# 03_-_28PINS_SCHEMATIC.net
KiCad netlist of a schematic drawn in Altium Designer
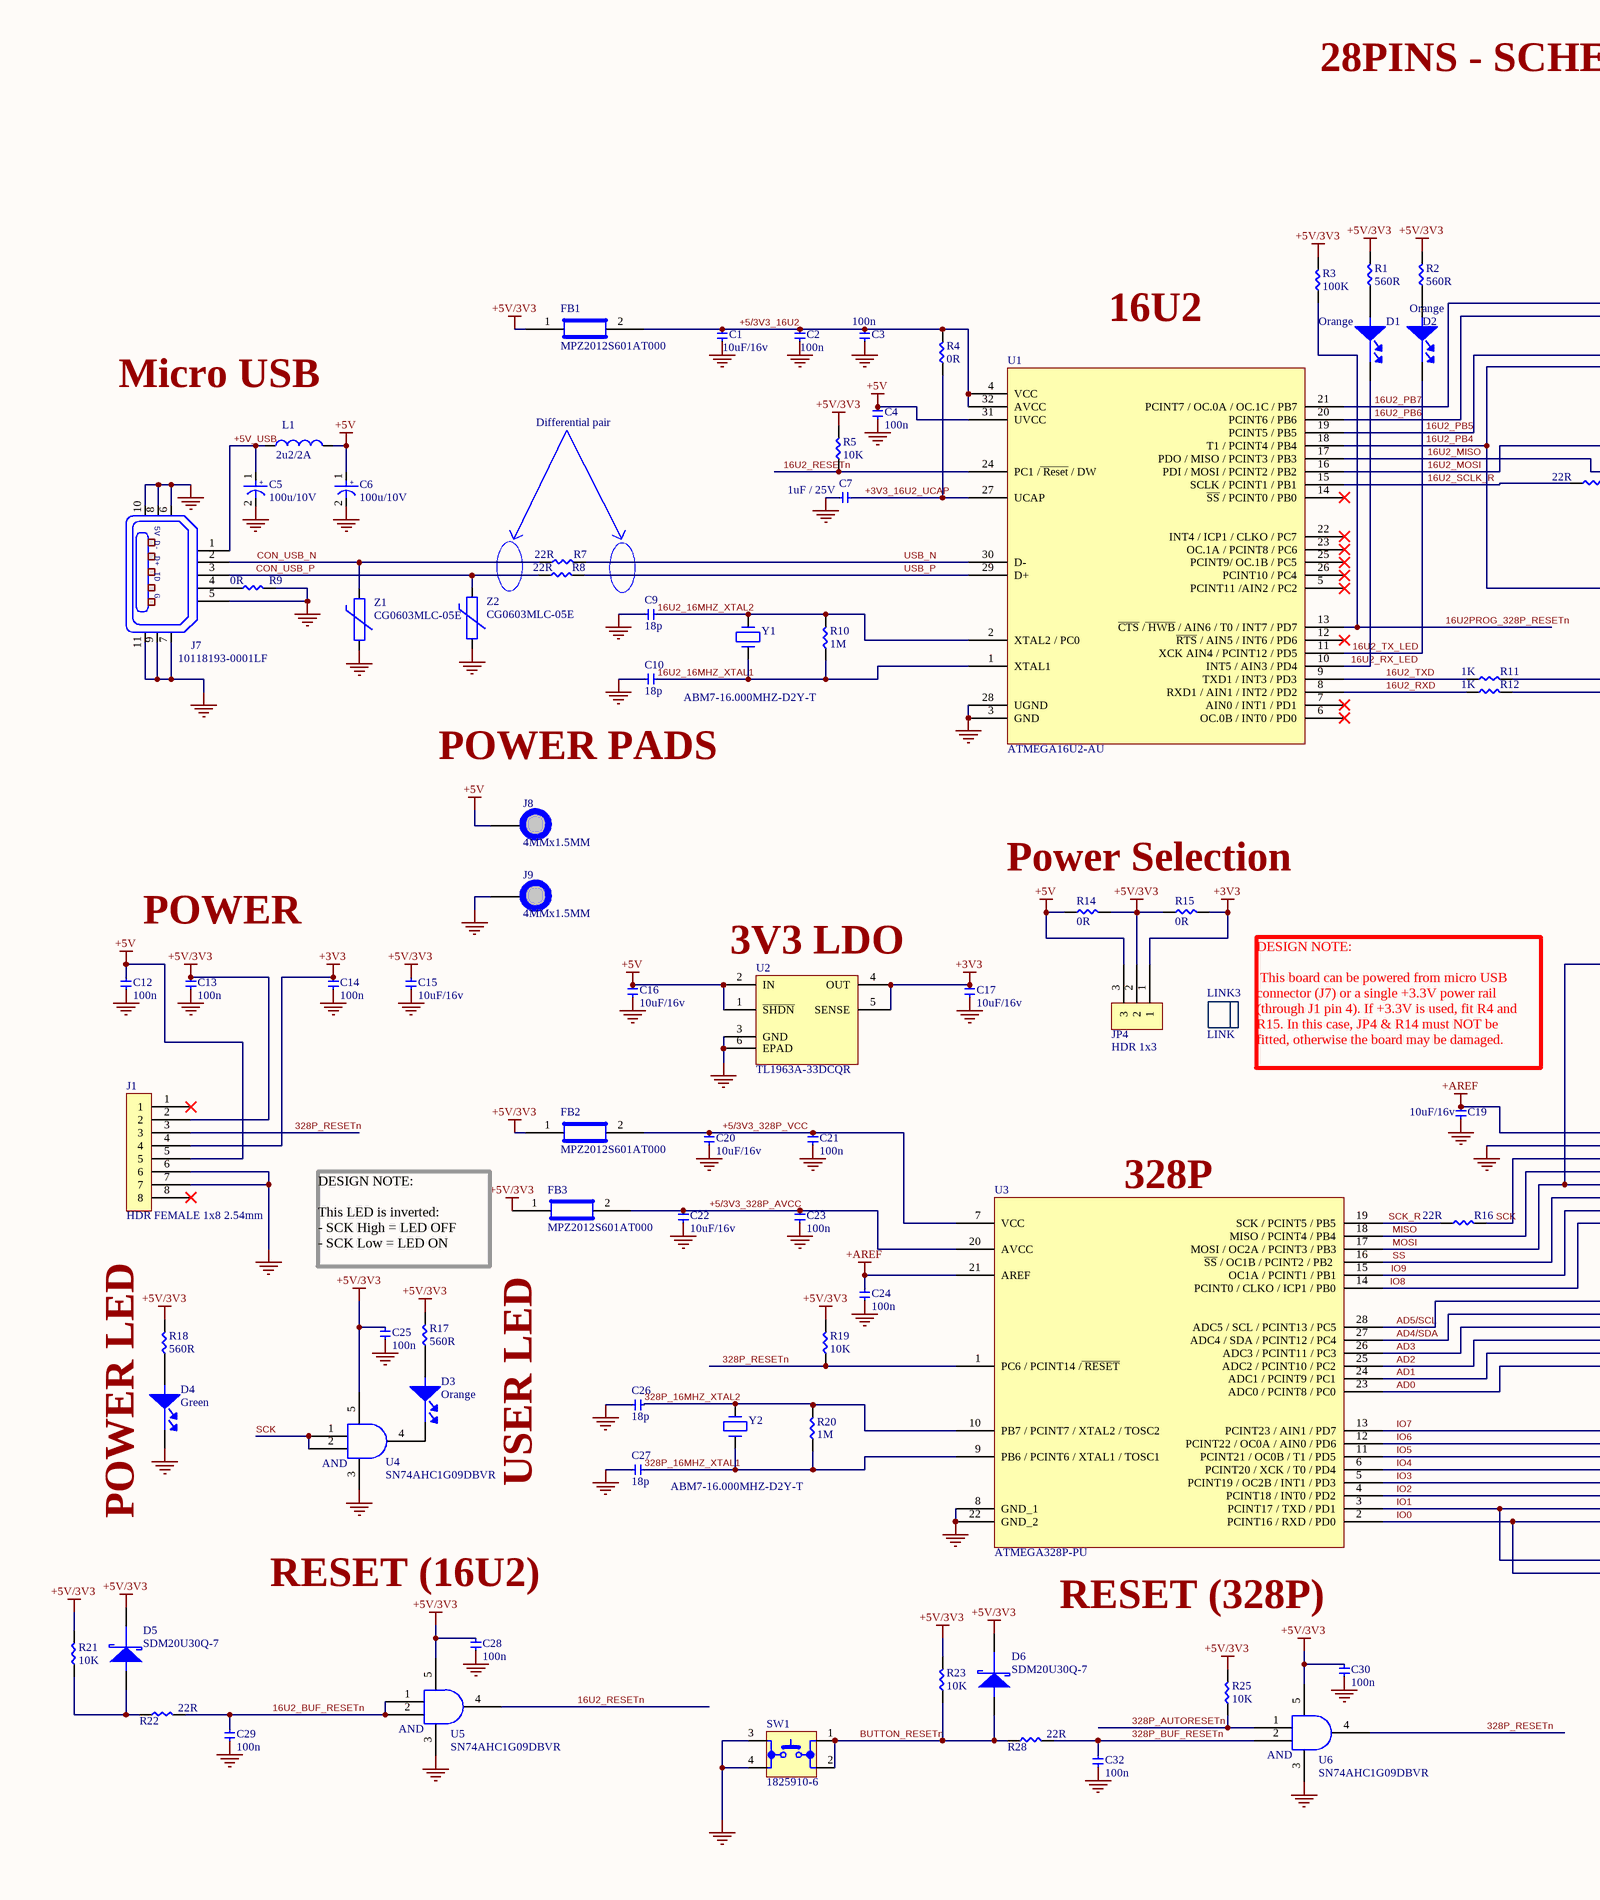
[diagram p0: [03] - 28PINS SCHEMATIC.SchDoc, left]
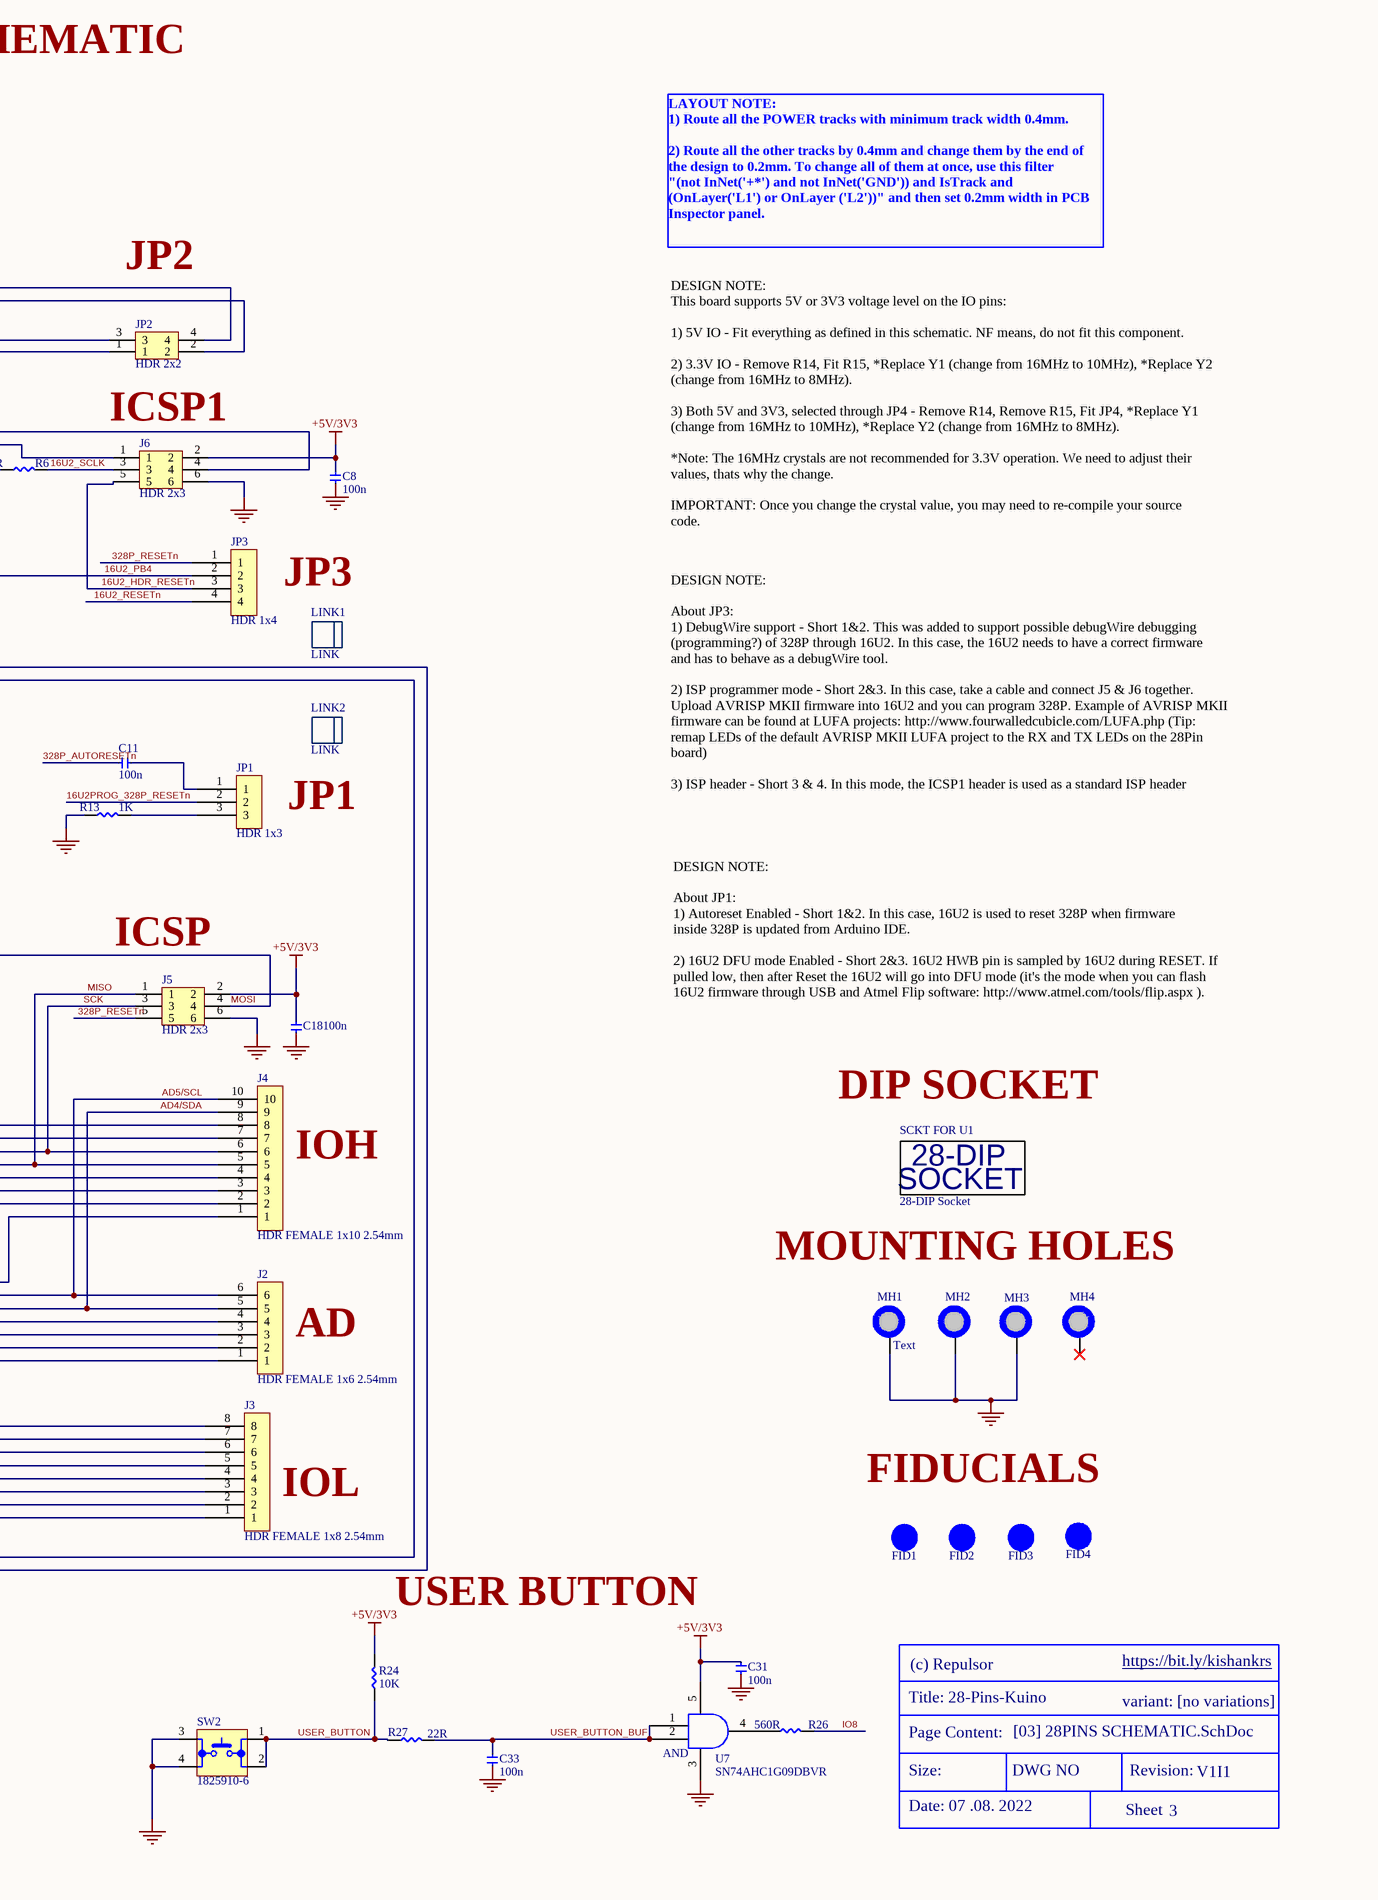
[diagram p1: [03] - 28PINS SCHEMATIC.SchDoc, right]

(export (version "E")
  (design (tool "Eeschema 10.0.6"))
  (components
    (comp (ref "C1")
      (value "10uF/16v")
      (footprint "C0805")
      (fields
        (field (name "MANUFACTURER") "TDK")
        (field (name "MANUFACTURER PART NUMBER") "CGA4J1X5R1C106K125AC")
        (field (name "TOLERANCE") "10%")
      )
      (libsource (lib "28Pins_Project_V1I1") (part "CGA4J1X5R1C106K125AC"))
    )
    (comp (ref "C2")
      (value "100n")
      (footprint "C0805")
      (description "C Series 0805 0.1 uF 50 V ±10 % Tolerance X7R SMT Multilayer Ceramic Capacitor")
      (fields
        (field (name "MANUFACTURER") "TDK")
        (field (name "MANUFACTURER PART NUMBER") "C2012X7R1H104K085AA")
      )
      (libsource (lib "28Pins_Project_V1I1") (part "C2012X7R1H104K085AA"))
    )
    (comp (ref "C3")
      (value "100n")
      (footprint "C0805")
      (description "C Series 0805 0.1 uF 50 V ±10 % Tolerance X7R SMT Multilayer Ceramic Capacitor")
      (fields
        (field (name "MANUFACTURER") "TDK")
        (field (name "MANUFACTURER PART NUMBER") "C2012X7R1H104K085AA")
      )
      (libsource (lib "28Pins_Project_V1I1") (part "C2012X7R1H104K085AA"))
    )
    (comp (ref "C4")
      (value "100n")
      (footprint "C0805")
      (description "C Series 0805 0.1 uF 50 V ±10 % Tolerance X7R SMT Multilayer Ceramic Capacitor")
      (fields
        (field (name "MANUFACTURER") "TDK")
        (field (name "MANUFACTURER PART NUMBER") "C2012X7R1H104K085AA")
      )
      (libsource (lib "28Pins_Project_V1I1") (part "C2012X7R1H104K085AA"))
    )
    (comp (ref "C5")
      (value "100u/10V")
      (footprint "C_ALU_C_SIZE")
      (description "CAP ALUM 100UF 20% 10V SMD")
      (fields
        (field (name "MANUFACTURER") "Panasonic")
        (field (name "MANUFACTURER PART NUMBER") "EEE-1AA101WR")
      )
      (libsource (lib "28Pins_Project_V1I1") (part "EEE-1AA101WR"))
    )
    (comp (ref "C6")
      (value "100u/10V")
      (footprint "C_ALU_C_SIZE")
      (description "CAP ALUM 100UF 20% 10V SMD")
      (fields
        (field (name "MANUFACTURER") "Panasonic")
        (field (name "MANUFACTURER PART NUMBER") "EEE-1AA101WR")
      )
      (libsource (lib "28Pins_Project_V1I1") (part "EEE-1AA101WR"))
    )
    (comp (ref "C7")
      (value "1uF / 25V")
      (footprint "C0805")
      (fields
        (field (name "MANUFACTURER") "TDK")
        (field (name "MANUFACTURER PART NUMBER") "C2012X5R1E105K125AA")
        (field (name "TOLERANCE") "10%")
      )
      (libsource (lib "28Pins_Project_V1I1") (part "C2012X5R1E105K125AA"))
    )
    (comp (ref "C8")
      (value "100n")
      (footprint "C0805")
      (description "C Series 0805 0.1 uF 50 V ±10 % Tolerance X7R SMT Multilayer Ceramic Capacitor")
      (fields
        (field (name "MANUFACTURER") "TDK")
        (field (name "MANUFACTURER PART NUMBER") "C2012X7R1H104K085AA")
      )
      (libsource (lib "28Pins_Project_V1I1") (part "C2012X7R1H104K085AA"))
    )
    (comp (ref "C9")
      (value "18p")
      (footprint "C0805")
      (description "Cap Ceramic 18pF 50V C0G 5% SMD 0805 125C Paper T/R")
      (fields
        (field (name "MANUFACTURER") "KEMET")
        (field (name "MANUFACTURER PART NUMBER") "C0805C180J5GACTU")
      )
      (libsource (lib "28Pins_Project_V1I1") (part "C0805C180J5GACTU"))
    )
    (comp (ref "C10")
      (value "18p")
      (footprint "C0805")
      (description "Cap Ceramic 18pF 50V C0G 5% SMD 0805 125C Paper T/R")
      (fields
        (field (name "MANUFACTURER") "KEMET")
        (field (name "MANUFACTURER PART NUMBER") "C0805C180J5GACTU")
      )
      (libsource (lib "28Pins_Project_V1I1") (part "C0805C180J5GACTU"))
    )
    (comp (ref "C11")
      (value "100n")
      (footprint "C0805")
      (description "C Series 0805 0.1 uF 50 V ±10 % Tolerance X7R SMT Multilayer Ceramic Capacitor")
      (fields
        (field (name "MANUFACTURER") "TDK")
        (field (name "MANUFACTURER PART NUMBER") "C2012X7R1H104K085AA")
      )
      (libsource (lib "28Pins_Project_V1I1") (part "C2012X7R1H104K085AA"))
    )
    (comp (ref "C12")
      (value "100n")
      (footprint "C0805")
      (description "C Series 0805 0.1 uF 50 V ±10 % Tolerance X7R SMT Multilayer Ceramic Capacitor")
      (fields
        (field (name "MANUFACTURER") "TDK")
        (field (name "MANUFACTURER PART NUMBER") "C2012X7R1H104K085AA")
      )
      (libsource (lib "28Pins_Project_V1I1") (part "C2012X7R1H104K085AA"))
    )
    (comp (ref "C13")
      (value "100n")
      (footprint "C0805")
      (description "C Series 0805 0.1 uF 50 V ±10 % Tolerance X7R SMT Multilayer Ceramic Capacitor")
      (fields
        (field (name "MANUFACTURER") "TDK")
        (field (name "MANUFACTURER PART NUMBER") "C2012X7R1H104K085AA")
      )
      (libsource (lib "28Pins_Project_V1I1") (part "C2012X7R1H104K085AA"))
    )
    (comp (ref "C14")
      (value "100n")
      (footprint "C0805")
      (description "C Series 0805 0.1 uF 50 V ±10 % Tolerance X7R SMT Multilayer Ceramic Capacitor")
      (fields
        (field (name "MANUFACTURER") "TDK")
        (field (name "MANUFACTURER PART NUMBER") "C2012X7R1H104K085AA")
      )
      (libsource (lib "28Pins_Project_V1I1") (part "C2012X7R1H104K085AA"))
    )
    (comp (ref "C15")
      (value "10uF/16v")
      (footprint "C0805")
      (fields
        (field (name "MANUFACTURER") "TDK")
        (field (name "MANUFACTURER PART NUMBER") "CGA4J1X5R1C106K125AC")
        (field (name "TOLERANCE") "10%")
      )
      (libsource (lib "28Pins_Project_V1I1") (part "CGA4J1X5R1C106K125AC"))
    )
    (comp (ref "C16")
      (value "10uF/16v")
      (footprint "C0805")
      (fields
        (field (name "MANUFACTURER") "TDK")
        (field (name "MANUFACTURER PART NUMBER") "CGA4J1X5R1C106K125AC")
        (field (name "TOLERANCE") "10%")
      )
      (libsource (lib "28Pins_Project_V1I1") (part "CGA4J1X5R1C106K125AC"))
    )
    (comp (ref "C17")
      (value "10uF/16v")
      (footprint "C0805")
      (fields
        (field (name "MANUFACTURER") "TDK")
        (field (name "MANUFACTURER PART NUMBER") "CGA4J1X5R1C106K125AC")
        (field (name "TOLERANCE") "10%")
      )
      (libsource (lib "28Pins_Project_V1I1") (part "CGA4J1X5R1C106K125AC"))
    )
    (comp (ref "C18")
      (value "100n")
      (footprint "C0805")
      (description "C Series 0805 0.1 uF 50 V ±10 % Tolerance X7R SMT Multilayer Ceramic Capacitor")
      (fields
        (field (name "MANUFACTURER") "TDK")
        (field (name "MANUFACTURER PART NUMBER") "C2012X7R1H104K085AA")
      )
      (libsource (lib "28Pins_Project_V1I1") (part "C2012X7R1H104K085AA"))
    )
    (comp (ref "C19")
      (value "10uF/16v")
      (footprint "C0805")
      (fields
        (field (name "MANUFACTURER") "TDK")
        (field (name "MANUFACTURER PART NUMBER") "CGA4J1X5R1C106K125AC")
        (field (name "TOLERANCE") "10%")
      )
      (libsource (lib "28Pins_Project_V1I1") (part "CGA4J1X5R1C106K125AC"))
    )
    (comp (ref "C20")
      (value "10uF/16v")
      (footprint "C0805")
      (fields
        (field (name "MANUFACTURER") "TDK")
        (field (name "MANUFACTURER PART NUMBER") "CGA4J1X5R1C106K125AC")
        (field (name "TOLERANCE") "10%")
      )
      (libsource (lib "28Pins_Project_V1I1") (part "CGA4J1X5R1C106K125AC"))
    )
    (comp (ref "C21")
      (value "100n")
      (footprint "C0805")
      (description "C Series 0805 0.1 uF 50 V ±10 % Tolerance X7R SMT Multilayer Ceramic Capacitor")
      (fields
        (field (name "MANUFACTURER") "TDK")
        (field (name "MANUFACTURER PART NUMBER") "C2012X7R1H104K085AA")
      )
      (libsource (lib "28Pins_Project_V1I1") (part "C2012X7R1H104K085AA"))
    )
    (comp (ref "C22")
      (value "10uF/16v")
      (footprint "C0805")
      (fields
        (field (name "MANUFACTURER") "TDK")
        (field (name "MANUFACTURER PART NUMBER") "CGA4J1X5R1C106K125AC")
        (field (name "TOLERANCE") "10%")
      )
      (libsource (lib "28Pins_Project_V1I1") (part "CGA4J1X5R1C106K125AC"))
    )
    (comp (ref "C23")
      (value "100n")
      (footprint "C0805")
      (description "C Series 0805 0.1 uF 50 V ±10 % Tolerance X7R SMT Multilayer Ceramic Capacitor")
      (fields
        (field (name "MANUFACTURER") "TDK")
        (field (name "MANUFACTURER PART NUMBER") "C2012X7R1H104K085AA")
      )
      (libsource (lib "28Pins_Project_V1I1") (part "C2012X7R1H104K085AA"))
    )
    (comp (ref "C24")
      (value "100n")
      (footprint "C0805")
      (description "C Series 0805 0.1 uF 50 V ±10 % Tolerance X7R SMT Multilayer Ceramic Capacitor")
      (fields
        (field (name "MANUFACTURER") "TDK")
        (field (name "MANUFACTURER PART NUMBER") "C2012X7R1H104K085AA")
      )
      (libsource (lib "28Pins_Project_V1I1") (part "C2012X7R1H104K085AA"))
    )
    (comp (ref "C25")
      (value "100n")
      (footprint "C0805")
      (description "C Series 0805 0.1 uF 50 V ±10 % Tolerance X7R SMT Multilayer Ceramic Capacitor")
      (fields
        (field (name "MANUFACTURER") "TDK")
        (field (name "MANUFACTURER PART NUMBER") "C2012X7R1H104K085AA")
      )
      (libsource (lib "28Pins_Project_V1I1") (part "C2012X7R1H104K085AA"))
    )
    (comp (ref "C26")
      (value "18p")
      (footprint "C0805")
      (description "Cap Ceramic 18pF 50V C0G 5% SMD 0805 125C Paper T/R")
      (fields
        (field (name "MANUFACTURER") "KEMET")
        (field (name "MANUFACTURER PART NUMBER") "C0805C180J5GACTU")
      )
      (libsource (lib "28Pins_Project_V1I1") (part "C0805C180J5GACTU"))
    )
    (comp (ref "C27")
      (value "18p")
      (footprint "C0805")
      (description "Cap Ceramic 18pF 50V C0G 5% SMD 0805 125C Paper T/R")
      (fields
        (field (name "MANUFACTURER") "KEMET")
        (field (name "MANUFACTURER PART NUMBER") "C0805C180J5GACTU")
      )
      (libsource (lib "28Pins_Project_V1I1") (part "C0805C180J5GACTU"))
    )
    (comp (ref "C28")
      (value "100n")
      (footprint "C0805")
      (description "C Series 0805 0.1 uF 50 V ±10 % Tolerance X7R SMT Multilayer Ceramic Capacitor")
      (fields
        (field (name "MANUFACTURER") "TDK")
        (field (name "MANUFACTURER PART NUMBER") "C2012X7R1H104K085AA")
      )
      (libsource (lib "28Pins_Project_V1I1") (part "C2012X7R1H104K085AA"))
    )
    (comp (ref "C29")
      (value "100n")
      (footprint "C0805")
      (description "C Series 0805 0.1 uF 50 V ±10 % Tolerance X7R SMT Multilayer Ceramic Capacitor")
      (fields
        (field (name "MANUFACTURER") "TDK")
        (field (name "MANUFACTURER PART NUMBER") "C2012X7R1H104K085AA")
      )
      (libsource (lib "28Pins_Project_V1I1") (part "C2012X7R1H104K085AA"))
    )
    (comp (ref "C30")
      (value "100n")
      (footprint "C0805")
      (description "C Series 0805 0.1 uF 50 V ±10 % Tolerance X7R SMT Multilayer Ceramic Capacitor")
      (fields
        (field (name "MANUFACTURER") "TDK")
        (field (name "MANUFACTURER PART NUMBER") "C2012X7R1H104K085AA")
      )
      (libsource (lib "28Pins_Project_V1I1") (part "C2012X7R1H104K085AA"))
    )
    (comp (ref "C31")
      (value "100n")
      (footprint "C0805")
      (description "C Series 0805 0.1 uF 50 V ±10 % Tolerance X7R SMT Multilayer Ceramic Capacitor")
      (fields
        (field (name "MANUFACTURER") "TDK")
        (field (name "MANUFACTURER PART NUMBER") "C2012X7R1H104K085AA")
      )
      (libsource (lib "28Pins_Project_V1I1") (part "C2012X7R1H104K085AA"))
    )
    (comp (ref "C32")
      (value "100n")
      (footprint "C0805")
      (description "C Series 0805 0.1 uF 50 V ±10 % Tolerance X7R SMT Multilayer Ceramic Capacitor")
      (fields
        (field (name "MANUFACTURER") "TDK")
        (field (name "MANUFACTURER PART NUMBER") "C2012X7R1H104K085AA")
      )
      (libsource (lib "28Pins_Project_V1I1") (part "C2012X7R1H104K085AA"))
    )
    (comp (ref "C33")
      (value "100n")
      (footprint "C0805")
      (description "C Series 0805 0.1 uF 50 V ±10 % Tolerance X7R SMT Multilayer Ceramic Capacitor")
      (fields
        (field (name "MANUFACTURER") "TDK")
        (field (name "MANUFACTURER PART NUMBER") "C2012X7R1H104K085AA")
      )
      (libsource (lib "28Pins_Project_V1I1") (part "C2012X7R1H104K085AA"))
    )
    (comp (ref "D1")
      (value "Orange")
      (footprint "LED_0603")
      (description "Smartled Orange Lc")
      (fields
        (field (name "MANUFACTURER") "Osram Opto")
        (field (name "MANUFACTURER PART NUMBER") "LOL29K-H2K1-24-Z")
      )
      (libsource (lib "28Pins_Project_V1I1") (part "LOL29K-H2K1-24-Z"))
    )
    (comp (ref "D2")
      (value "Orange")
      (footprint "LED_0603")
      (description "Smartled Orange Lc")
      (fields
        (field (name "MANUFACTURER") "Osram Opto")
        (field (name "MANUFACTURER PART NUMBER") "LOL29K-H2K1-24-Z")
      )
      (libsource (lib "28Pins_Project_V1I1") (part "LOL29K-H2K1-24-Z"))
    )
    (comp (ref "D3")
      (value "Orange")
      (footprint "LED_0603")
      (description "Smartled Orange Lc")
      (fields
        (field (name "MANUFACTURER") "Osram Opto")
        (field (name "MANUFACTURER PART NUMBER") "LOL29K-H2K1-24-Z")
      )
      (libsource (lib "28Pins_Project_V1I1") (part "LOL29K-H2K1-24-Z"))
    )
    (comp (ref "D4")
      (value "Green")
      (footprint "LED_0603")
      (description "Green 574nm LED Indication - Discrete 1.9V 0603 (1608 Metric)")
      (fields (field (name "MANUFACTURER") "Bivar") (field (name "MANUFACTURER PART NUMBER") "SM0603GCL"))
      (libsource (lib "28Pins_Project_V1I1") (part "SM0603GCL"))
    )
    (comp (ref "D5")
      (value "SDM20U30Q-7")
      (footprint "SOD523")
      (description "Schottky Rectifier, 30V, 0.2A, Sod-523 Rohs Compliant: Yes")
      (fields (field (name "MANUFACTURER") "Diodes"))
      (libsource (lib "28Pins_Project_V1I1") (part "SDM20U30Q-7"))
    )
    (comp (ref "D6")
      (value "SDM20U30Q-7")
      (footprint "SOD523")
      (description "Schottky Rectifier, 30V, 0.2A, Sod-523 Rohs Compliant: Yes")
      (fields (field (name "MANUFACTURER") "Diodes"))
      (libsource (lib "28Pins_Project_V1I1") (part "SDM20U30Q-7"))
    )
    (comp (ref "FB1")
      (value "MPZ2012S601AT000")
      (footprint "C0805")
      (description "0805 600Ω ±25% DCR=0.1Ω 2A")
      (fields (field (name "MANUFACTURER") "TDK"))
      (libsource (lib "28Pins_Project_V1I1") (part "MPZ2012S601AT000"))
    )
    (comp (ref "FB2")
      (value "MPZ2012S601AT000")
      (footprint "C0805")
      (description "0805 600Ω ±25% DCR=0.1Ω 2A")
      (fields (field (name "MANUFACTURER") "TDK"))
      (libsource (lib "28Pins_Project_V1I1") (part "MPZ2012S601AT000"))
    )
    (comp (ref "FB3")
      (value "MPZ2012S601AT000")
      (footprint "C0805")
      (description "0805 600Ω ±25% DCR=0.1Ω 2A")
      (fields (field (name "MANUFACTURER") "TDK"))
      (libsource (lib "28Pins_Project_V1I1") (part "MPZ2012S601AT000"))
    )
    (comp (ref "FID1")
      (value "FID_1MMC")
      (footprint "FID_40x120D")
      (description "Fiducial 40mil Diameter, 120mil Mask")
      (libsource (lib "28Pins_Project_V1I1") (part "FID_1MMC"))
    )
    (comp (ref "FID2")
      (value "FID_1MMC")
      (footprint "FID_40x120D")
      (description "Fiducial 40mil Diameter, 120mil Mask")
      (libsource (lib "28Pins_Project_V1I1") (part "FID_1MMC"))
    )
    (comp (ref "FID3")
      (value "FID_1MMC")
      (footprint "FID_40x120D")
      (description "Fiducial 40mil Diameter, 120mil Mask")
      (libsource (lib "28Pins_Project_V1I1") (part "FID_1MMC"))
    )
    (comp (ref "FID4")
      (value "FID_1MMC")
      (footprint "FID_40x120D")
      (description "Fiducial 40mil Diameter, 120mil Mask")
      (libsource (lib "28Pins_Project_V1I1") (part "FID_1MMC"))
    )
    (comp (ref "J1")
      (value "HDR FEMALE 1x8 2.54mm")
      (footprint "Hdr_Female_1x8_2.54mm")
      (description "2.54mm (0.1\") Pitch SIL Vertical PC Tail Socket Assembly, selective gold + tin, 8 contacts")
      (fields (field (name "MANUFACTURER") "Harwin") (field (name "MANUFACTURER PART NUMBER") "M20-7820842"))
      (libsource (lib "") (part "M20-7820842_1"))
    )
    (comp (ref "J2")
      (value "HDR FEMALE 1x6 2.54mm")
      (footprint "Hdr_Female_1x6_2.54mm")
      (description "2.54mm (0.1\") Pitch SIL Vertical PC Tail Socket Assembly, tin, 6 contacts")
      (fields (field (name "MANUFACTURER") "Harwin") (field (name "MANUFACTURER PART NUMBER") "M20-7820646"))
      (libsource (lib "28Pins_Project_V1I1") (part "M20-7820646"))
    )
    (comp (ref "J3")
      (value "HDR FEMALE 1x8 2.54mm")
      (footprint "Hdr_Female_1x8_2.54mm")
      (description "2.54mm (0.1\") Pitch SIL Vertical PC Tail Socket Assembly, selective gold + tin, 8 contacts")
      (fields (field (name "MANUFACTURER") "Harwin") (field (name "MANUFACTURER PART NUMBER") "M20-7820842"))
      (libsource (lib "28Pins_Project_V1I1") (part "M20-7820842"))
    )
    (comp (ref "J4")
      (value "HDR FEMALE 1x10 2.54mm")
      (footprint "Hdr_Female_1x10_2.54mm")
      (description "2.54mm (0.1\") Pitch SIL Vertical PC Tail Socket Assembly, tin, 10 contacts")
      (fields (field (name "MANUFACTURER") "Harwin") (field (name "MANUFACTURER PART NUMBER") "M20-7821046"))
      (libsource (lib "28Pins_Project_V1I1") (part "M20-7821046"))
    )
    (comp (ref "J5")
      (value "HDR 2x3")
      (footprint "HDR_2x3_2.54MM")
      (description "2 Row 6 Position 2.54 mm Straight Unshrouded Male Pin Header")
      (fields
        (field (name "MANUFACTURER") "Amphenol Communications Solutions")
        (field (name "MANUFACTURER PART NUMBER") "67997-206HLF")
      )
      (libsource (lib "28Pins_Project_V1I1") (part "67997-206HLF"))
    )
    (comp (ref "J6")
      (value "HDR 2x3")
      (footprint "HDR_2x3_2.54MM")
      (description "2 Row 6 Position 2.54 mm Straight Unshrouded Male Pin Header")
      (fields
        (field (name "MANUFACTURER") "Amphenol Communications Solutions")
        (field (name "MANUFACTURER PART NUMBER") "67997-206HLF")
      )
      (libsource (lib "28Pins_Project_V1I1") (part "67997-206HLF"))
    )
    (comp (ref "J7")
      (value "10118193-0001LF")
      (footprint "10118193")
      (description "FCI Right Angle Surface Mount Mount Female USB Connector; 100 V ac; 1.8A")
      (fields (field (name "MANUFACTURER") "Amphenol ICC / FCI"))
      (libsource (lib "28Pins_Project_V1I1") (part "10118193-0001LF"))
    )
    (comp (ref "J8")
      (value "4MMx1.5MM")
      (footprint "PAD_WITH_HOLE_4MMx1.5MM")
      (description "pad with a hole 4mm x 1.5 mm")
      (libsource (lib "28Pins_Project_V1I1") (part "PAD_WITH_HOLE_4MMx1.5MM"))
    )
    (comp (ref "J9")
      (value "4MMx1.5MM")
      (footprint "PAD_WITH_HOLE_4MMx1.5MM")
      (description "pad with a hole 4mm x 1.5 mm")
      (libsource (lib "28Pins_Project_V1I1") (part "PAD_WITH_HOLE_4MMx1.5MM"))
    )
    (comp (ref "JP1")
      (value "HDR 1x3")
      (footprint "Hdr_1x3_2.54mm")
      (description "Conn Unshrouded Header HDR 3 POS 2.54mm Solder ST Top Entry Thru-Hole BergStik® Automotive Bulk")
      (fields
        (field (name "MANUFACTURER") "Amphenol ICC / FCI")
        (field (name "MANUFACTURER PART NUMBER") "68000-103HLF")
      )
      (libsource (lib "28Pins_Project_V1I1") (part "68000-103HLF"))
    )
    (comp (ref "JP2")
      (value "HDR 2x2")
      (footprint "HDR_2x2_2.54MM")
      (description "Conn Unshrouded Header HDR 4 POS 2.54mm Solder ST Thru-Hole Poly Bag")
      (fields
        (field (name "MANUFACTURER") "Amphenol ICC / FCI")
        (field (name "MANUFACTURER PART NUMBER") "68491-104HLF")
      )
      (libsource (lib "28Pins_Project_V1I1") (part "68491-104HLF"))
    )
    (comp (ref "JP3")
      (value "HDR 1x4")
      (footprint "HDR_1x4_2.54mm")
      (description "Conn Unshrouded Header HDR 4 POS 2.54mm Solder ST Thru-Hole Bag")
      (fields
        (field (name "MANUFACTURER") "Amphenol ICC / FCI")
        (field (name "MANUFACTURER PART NUMBER") "68001-204HLF")
      )
      (libsource (lib "28Pins_Project_V1I1") (part "68001-204HLF"))
    )
    (comp (ref "JP4")
      (value "HDR 1x3")
      (footprint "Hdr_1x3_2.54mm")
      (description "Conn Unshrouded Header HDR 3 POS 2.54mm Solder ST Top Entry Thru-Hole BergStik® Automotive Bulk")
      (fields
        (field (name "MANUFACTURER") "Amphenol ICC / FCI")
        (field (name "MANUFACTURER PART NUMBER") "68000-103HLF")
      )
      (libsource (lib "") (part "68000-103HLF_1"))
    )
    (comp (ref "L1")
      (value "2u2/2A")
      (footprint "C1210_IND")
      (description "Inductor RF Chip Wirewound 2.2uH 20% 100KHz 1.13A 0.104Ohm DCR 1210 T/R")
      (fields
        (field (name "MANUFACTURER") "KEMET")
        (field (name "MANUFACTURER PART NUMBER") "L1210R2R2MDWIT")
      )
      (libsource (lib "28Pins_Project_V1I1") (part "L1210R2R2MDWIT"))
    )
    (comp (ref "LINK1")
      (value "LINK")
      (description "2 Position 2.54 mm Centerline Single Circuit Open Top Jumper")
      (fields
        (field (name "MANUFACTURER") "Sullins")
        (field (name "MANUFACTURER PART NUMBER") "QPC02SXGN-RC")
      )
      (libsource (lib "28Pins_Project_V1I1") (part "QPC02SXGN-RC"))
    )
    (comp (ref "LINK2")
      (value "LINK")
      (description "2 Position 2.54 mm Centerline Single Circuit Open Top Jumper")
      (fields
        (field (name "MANUFACTURER") "Sullins")
        (field (name "MANUFACTURER PART NUMBER") "QPC02SXGN-RC")
      )
      (libsource (lib "28Pins_Project_V1I1") (part "QPC02SXGN-RC"))
    )
    (comp (ref "LINK3")
      (value "LINK")
      (description "2 Position 2.54 mm Centerline Single Circuit Open Top Jumper")
      (fields
        (field (name "MANUFACTURER") "Sullins")
        (field (name "MANUFACTURER PART NUMBER") "QPC02SXGN-RC")
      )
      (libsource (lib "28Pins_Project_V1I1") (part "QPC02SXGN-RC"))
    )
    (comp (ref "MH1")
      (value "MH_7.4MMC_3.2MMD")
      (footprint "MH_7.4MMD_3.2MMD")
      (description "Mounting Hole 7.4mm Diameter, 3.2mm Drill")
      (libsource (lib "28Pins_Project_V1I1") (part "MH_7.4MMC_3.2MMD"))
    )
    (comp (ref "MH2")
      (value "MH_7.4MMC_3.2MMD")
      (footprint "MH_7.4MMD_3.2MMD")
      (description "Mounting Hole 7.4mm Diameter, 3.2mm Drill")
      (libsource (lib "28Pins_Project_V1I1") (part "MH_7.4MMC_3.2MMD"))
    )
    (comp (ref "MH3")
      (value "MH_7.4MMC_3.2MMD")
      (footprint "MH_7.4MMD_3.2MMD")
      (description "Mounting Hole 7.4mm Diameter, 3.2mm Drill")
      (libsource (lib "28Pins_Project_V1I1") (part "MH_7.4MMC_3.2MMD"))
    )
    (comp (ref "MH4")
      (value "MH_7.4MMNC_3.2MMD")
      (footprint "MH_7.4MMNC_3.2MMD_NON_COPPER_NPTH")
      (description "Hole 7.4mm Diameter(Non Copper), 3.2mm Drill NPTH")
      (libsource (lib "28Pins_Project_V1I1") (part "MH_7.4MMNC_3.2MMD"))
    )
    (comp (ref "R1")
      (value "560R")
      (footprint "R0805")
      (description "Res General Purpose Thick Film 0805 560 Ohm 1% 1/8W ±100ppm/°C Molded Paper T/R")
      (fields
        (field (name "MANUFACTURER") "Yageo")
        (field (name "MANUFACTURER PART NUMBER") "RC0805FR-07560RL")
      )
      (libsource (lib "28Pins_Project_V1I1") (part "RC0805FR-07560RL"))
    )
    (comp (ref "R2")
      (value "560R")
      (footprint "R0805")
      (description "Res General Purpose Thick Film 0805 560 Ohm 1% 1/8W ±100ppm/°C Molded Paper T/R")
      (fields
        (field (name "MANUFACTURER") "Yageo")
        (field (name "MANUFACTURER PART NUMBER") "RC0805FR-07560RL")
      )
      (libsource (lib "28Pins_Project_V1I1") (part "RC0805FR-07560RL"))
    )
    (comp (ref "R3")
      (value "100K")
      (footprint "R0805")
      (description "Res Thick Film 0805 100K Ohm 1% 1/8W ±100ppm/°C Molded SMD Paper T/R")
      (fields
        (field (name "MANUFACTURER") "Yageo")
        (field (name "MANUFACTURER PART NUMBER") "RC0805FR-07100KL")
      )
      (libsource (lib "28Pins_Project_V1I1") (part "RC0805FR-07100KL"))
    )
    (comp (ref "R4")
      (value "0R")
      (footprint "R0805")
      (description "Surface Mount Thick Film Resistor, RC Series, 125 mW, - 5%, 150 V, 0805 [2012 Metric]")
      (fields
        (field (name "MANUFACTURER") "Yageo")
        (field (name "MANUFACTURER PART NUMBER") "RC0805JR-070RL")
      )
      (libsource (lib "28Pins_Project_V1I1") (part "RC0805JR-070RL"))
    )
    (comp (ref "R5")
      (value "10K")
      (footprint "R0805")
      (description "Res Thick Film 0805 10K Ohm 1% 0.125W(1/8W) +/-100ppm/C Epoxy Pad SMD T/R")
      (fields
        (field (name "MANUFACTURER") "Yageo")
        (field (name "MANUFACTURER PART NUMBER") "RC0805FR-0710KL")
      )
      (libsource (lib "28Pins_Project_V1I1") (part "RC0805FR-0710KL"))
    )
    (comp (ref "R6")
      (value "22R")
      (footprint "R0805")
      (description "Res Thick Film 0805 220 Ohm 1% 1/8W +/-100ppm/ßC Molded SMD Paper T/R")
      (fields
        (field (name "MANUFACTURER") "Yageo")
        (field (name "MANUFACTURER PART NUMBER") "RC0805FR-07220RL")
      )
      (libsource (lib "28Pins_Project_V1I1") (part "RC0805FR-07220RL"))
    )
    (comp (ref "R7")
      (value "22R")
      (footprint "R0805")
      (description "Res Thick Film 0805 220 Ohm 1% 1/8W +/-100ppm/ßC Molded SMD Paper T/R")
      (fields
        (field (name "MANUFACTURER") "Yageo")
        (field (name "MANUFACTURER PART NUMBER") "RC0805FR-07220RL")
      )
      (libsource (lib "28Pins_Project_V1I1") (part "RC0805FR-07220RL"))
    )
    (comp (ref "R8")
      (value "22R")
      (footprint "R0805")
      (description "Res Thick Film 0805 220 Ohm 1% 1/8W +/-100ppm/ßC Molded SMD Paper T/R")
      (fields
        (field (name "MANUFACTURER") "Yageo")
        (field (name "MANUFACTURER PART NUMBER") "RC0805FR-07220RL")
      )
      (libsource (lib "28Pins_Project_V1I1") (part "RC0805FR-07220RL"))
    )
    (comp (ref "R9")
      (value "0R")
      (footprint "R0805")
      (description "Surface Mount Thick Film Resistor, RC Series, 125 mW, - 5%, 150 V, 0805 [2012 Metric]")
      (fields
        (field (name "MANUFACTURER") "Yageo")
        (field (name "MANUFACTURER PART NUMBER") "RC0805JR-070RL")
      )
      (libsource (lib "28Pins_Project_V1I1") (part "RC0805JR-070RL"))
    )
    (comp (ref "R10")
      (value "1M")
      (footprint "R0805")
      (description "Res Thick Film 0805 1M Ohm 1% 0.125W(1/8W) ±100ppm/C Pad SMD T/R")
      (fields
        (field (name "MANUFACTURER") "Yageo Phycomp")
        (field (name "MANUFACTURER PART NUMBER") "RC0805FR-071ML")
      )
      (libsource (lib "28Pins_Project_V1I1") (part "RC0805FR-071ML"))
    )
    (comp (ref "R11")
      (value "1K")
      (footprint "R0805")
      (description "RES SMD 1K OHM 1% 1/8W 0805")
      (fields
        (field (name "MANUFACTURER") "Yageo")
        (field (name "MANUFACTURER PART NUMBER") "RC0805FR-071KL")
      )
      (libsource (lib "28Pins_Project_V1I1") (part "RC0805FR-071KL"))
    )
    (comp (ref "R12")
      (value "1K")
      (footprint "R0805")
      (description "RES SMD 1K OHM 1% 1/8W 0805")
      (fields
        (field (name "MANUFACTURER") "Yageo")
        (field (name "MANUFACTURER PART NUMBER") "RC0805FR-071KL")
      )
      (libsource (lib "28Pins_Project_V1I1") (part "RC0805FR-071KL"))
    )
    (comp (ref "R13")
      (value "1K")
      (footprint "R0805")
      (description "RES SMD 1K OHM 1% 1/8W 0805")
      (fields
        (field (name "MANUFACTURER") "Yageo")
        (field (name "MANUFACTURER PART NUMBER") "RC0805FR-071KL")
      )
      (libsource (lib "28Pins_Project_V1I1") (part "RC0805FR-071KL"))
    )
    (comp (ref "R14")
      (value "0R")
      (footprint "R0805")
      (description "Surface Mount Thick Film Resistor, RC Series, 125 mW, - 5%, 150 V, 0805 [2012 Metric]")
      (fields
        (field (name "MANUFACTURER") "Yageo")
        (field (name "MANUFACTURER PART NUMBER") "RC0805JR-070RL")
      )
      (libsource (lib "28Pins_Project_V1I1") (part "RC0805JR-070RL"))
    )
    (comp (ref "R15")
      (value "0R")
      (footprint "R0805")
      (description "Surface Mount Thick Film Resistor, RC Series, 125 mW, - 5%, 150 V, 0805 [2012 Metric]")
      (fields
        (field (name "MANUFACTURER") "Yageo")
        (field (name "MANUFACTURER PART NUMBER") "RC0805JR-070RL")
      )
      (libsource (lib "28Pins_Project_V1I1") (part "RC0805JR-070RL"))
    )
    (comp (ref "R16")
      (value "22R")
      (footprint "R0805")
      (description "Res Thick Film 0805 220 Ohm 1% 1/8W +/-100ppm/ßC Molded SMD Paper T/R")
      (fields
        (field (name "MANUFACTURER") "Yageo")
        (field (name "MANUFACTURER PART NUMBER") "RC0805FR-07220RL")
      )
      (libsource (lib "28Pins_Project_V1I1") (part "RC0805FR-07220RL"))
    )
    (comp (ref "R17")
      (value "560R")
      (footprint "R0805")
      (description "Res General Purpose Thick Film 0805 560 Ohm 1% 1/8W ±100ppm/°C Molded Paper T/R")
      (fields
        (field (name "MANUFACTURER") "Yageo")
        (field (name "MANUFACTURER PART NUMBER") "RC0805FR-07560RL")
      )
      (libsource (lib "28Pins_Project_V1I1") (part "RC0805FR-07560RL"))
    )
    (comp (ref "R18")
      (value "560R")
      (footprint "R0805")
      (description "Res General Purpose Thick Film 0805 560 Ohm 1% 1/8W ±100ppm/°C Molded Paper T/R")
      (fields
        (field (name "MANUFACTURER") "Yageo")
        (field (name "MANUFACTURER PART NUMBER") "RC0805FR-07560RL")
      )
      (libsource (lib "28Pins_Project_V1I1") (part "RC0805FR-07560RL"))
    )
    (comp (ref "R19")
      (value "10K")
      (footprint "R0805")
      (description "Res Thick Film 0805 10K Ohm 1% 0.125W(1/8W) +/-100ppm/C Epoxy Pad SMD T/R")
      (fields
        (field (name "MANUFACTURER") "Yageo")
        (field (name "MANUFACTURER PART NUMBER") "RC0805FR-0710KL")
      )
      (libsource (lib "28Pins_Project_V1I1") (part "RC0805FR-0710KL"))
    )
    (comp (ref "R20")
      (value "1M")
      (footprint "R0805")
      (description "Res Thick Film 0805 1M Ohm 1% 0.125W(1/8W) ±100ppm/C Pad SMD T/R")
      (fields
        (field (name "MANUFACTURER") "Yageo Phycomp")
        (field (name "MANUFACTURER PART NUMBER") "RC0805FR-071ML")
      )
      (libsource (lib "28Pins_Project_V1I1") (part "RC0805FR-071ML"))
    )
    (comp (ref "R21")
      (value "10K")
      (footprint "R0805")
      (description "Res Thick Film 0805 10K Ohm 1% 0.125W(1/8W) +/-100ppm/C Epoxy Pad SMD T/R")
      (fields
        (field (name "MANUFACTURER") "Yageo")
        (field (name "MANUFACTURER PART NUMBER") "RC0805FR-0710KL")
      )
      (libsource (lib "28Pins_Project_V1I1") (part "RC0805FR-0710KL"))
    )
    (comp (ref "R22")
      (value "22R")
      (footprint "R0805")
      (description "Res Thick Film 0805 220 Ohm 1% 1/8W +/-100ppm/ßC Molded SMD Paper T/R")
      (fields
        (field (name "MANUFACTURER") "Yageo")
        (field (name "MANUFACTURER PART NUMBER") "RC0805FR-07220RL")
      )
      (libsource (lib "28Pins_Project_V1I1") (part "RC0805FR-07220RL"))
    )
    (comp (ref "R23")
      (value "10K")
      (footprint "R0805")
      (description "Res Thick Film 0805 10K Ohm 1% 0.125W(1/8W) +/-100ppm/C Epoxy Pad SMD T/R")
      (fields
        (field (name "MANUFACTURER") "Yageo")
        (field (name "MANUFACTURER PART NUMBER") "RC0805FR-0710KL")
      )
      (libsource (lib "28Pins_Project_V1I1") (part "RC0805FR-0710KL"))
    )
    (comp (ref "R24")
      (value "10K")
      (footprint "R0805")
      (description "Res Thick Film 0805 10K Ohm 1% 0.125W(1/8W) +/-100ppm/C Epoxy Pad SMD T/R")
      (fields
        (field (name "MANUFACTURER") "Yageo")
        (field (name "MANUFACTURER PART NUMBER") "RC0805FR-0710KL")
      )
      (libsource (lib "28Pins_Project_V1I1") (part "RC0805FR-0710KL"))
    )
    (comp (ref "R25")
      (value "10K")
      (footprint "R0805")
      (description "Res Thick Film 0805 10K Ohm 1% 0.125W(1/8W) +/-100ppm/C Epoxy Pad SMD T/R")
      (fields
        (field (name "MANUFACTURER") "Yageo")
        (field (name "MANUFACTURER PART NUMBER") "RC0805FR-0710KL")
      )
      (libsource (lib "28Pins_Project_V1I1") (part "RC0805FR-0710KL"))
    )
    (comp (ref "R26")
      (value "560R")
      (footprint "R0805")
      (description "Res General Purpose Thick Film 0805 560 Ohm 1% 1/8W ±100ppm/°C Molded Paper T/R")
      (fields
        (field (name "MANUFACTURER") "Yageo")
        (field (name "MANUFACTURER PART NUMBER") "RC0805FR-07560RL")
      )
      (libsource (lib "28Pins_Project_V1I1") (part "RC0805FR-07560RL"))
    )
    (comp (ref "R27")
      (value "22R")
      (footprint "R0805")
      (description "Res Thick Film 0805 220 Ohm 1% 1/8W +/-100ppm/ßC Molded SMD Paper T/R")
      (fields
        (field (name "MANUFACTURER") "Yageo")
        (field (name "MANUFACTURER PART NUMBER") "RC0805FR-07220RL")
      )
      (libsource (lib "28Pins_Project_V1I1") (part "RC0805FR-07220RL"))
    )
    (comp (ref "R28")
      (value "22R")
      (footprint "R0805")
      (description "Res Thick Film 0805 220 Ohm 1% 1/8W +/-100ppm/ßC Molded SMD Paper T/R")
      (fields
        (field (name "MANUFACTURER") "Yageo")
        (field (name "MANUFACTURER PART NUMBER") "RC0805FR-07220RL")
      )
      (libsource (lib "28Pins_Project_V1I1") (part "RC0805FR-07220RL"))
    )
    (comp (ref "SCKT FOR U1")
      (value "28-DIP Socket")
      (footprint "28_DIP_7.6mm_SOCKET")
      (description "Socket DIP 28Cnts DualWipe 0.3InSpc. PhosphorBronze Nickel KinkedTail 4800Series")
      (fields (field (name "MANUFACTURER") "3M") (field (name "MANUFACTURER PART NUMBER") "4828-3004-CP"))
      (libsource (lib "28Pins_Project_V1I1") (part "4828-3004-CP"))
    )
    (comp (ref "SW1")
      (value "1825910-6")
      (footprint "1825910-6")
      (description "Switch Tactile OFF (ON) SPST Round Button PC Pins 0.05A 24VDC 1.57N Thru-Hole Loose")
      (fields (field (name "MANUFACTURER") "TE Connectivity Alcoswitch"))
      (libsource (lib "28Pins_Project_V1I1") (part "1825910-6"))
    )
    (comp (ref "SW2")
      (value "1825910-6")
      (footprint "1825910-6")
      (description "Switch Tactile OFF (ON) SPST Round Button PC Pins 0.05A 24VDC 1.57N Thru-Hole Loose")
      (fields (field (name "MANUFACTURER") "TE Connectivity Alcoswitch"))
      (libsource (lib "28Pins_Project_V1I1") (part "1825910-6"))
    )
    (comp (ref "U1")
      (value "ATMEGA16U2-AU")
      (footprint "TQFP32")
      (description "8-bit AVR MCU, 16 KB, 512 Bytes, 16 MHz, 2.7 to 5.5V, TQFP-32, RoHS")
      (fields (field (name "MANUFACTURER") "Microchip / Atmel"))
      (libsource (lib "28Pins_Project_V1I1") (part "ATMEGA16U2-AU"))
    )
    (comp (ref "U2")
      (value "TL1963A-33DCQR")
      (footprint "DCQ(R-PDSO-G6)")
      (description "LDO Regulator Pos 3.3V 1.5A 6-Pin(5+Tab) SOT-223 T/R")
      (fields (field (name "MANUFACTURER") "Texas Instruments"))
      (libsource (lib "28Pins_Project_V1I1") (part "TL1963A-33DCQR"))
    )
    (comp (ref "U3")
      (value "ATMEGA328P-PU")
      (footprint "28_DIP_7.62mm")
      (description "ATMEGA328P-PU; 8 bit Microcontroller AVR 20MHz 1; 32kb Flash; 2kb RAM; I2C SPI 2")
      (fields (field (name "MANUFACTURER") "Microchip / Atmel"))
      (libsource (lib "28Pins_Project_V1I1") (part "ATMEGA328P-PU"))
    )
    (comp (ref "U4")
      (value "SN74AHC1G09DBVR")
      (footprint "DBV_SOT_23_S")
      (description "Single 2-input, 2-V to 5.5-V AND gate with open-drain outputs 5-SOT-23 -55 to 125")
      (fields (field (name "MANUFACTURER") "Texas Instruments"))
      (libsource (lib "28Pins_Project_V1I1") (part "SN74AHC1G09DBVR"))
    )
    (comp (ref "U5")
      (value "SN74AHC1G09DBVR")
      (footprint "DBV_SOT_23_S")
      (description "Single 2-input, 2-V to 5.5-V AND gate with open-drain outputs 5-SOT-23 -55 to 125")
      (fields (field (name "MANUFACTURER") "Texas Instruments"))
      (libsource (lib "28Pins_Project_V1I1") (part "SN74AHC1G09DBVR"))
    )
    (comp (ref "U6")
      (value "SN74AHC1G09DBVR")
      (footprint "DBV_SOT_23_S")
      (description "Single 2-input, 2-V to 5.5-V AND gate with open-drain outputs 5-SOT-23 -55 to 125")
      (fields (field (name "MANUFACTURER") "Texas Instruments"))
      (libsource (lib "28Pins_Project_V1I1") (part "SN74AHC1G09DBVR"))
    )
    (comp (ref "U7")
      (value "SN74AHC1G09DBVR")
      (footprint "DBV_SOT_23_S")
      (description "Single 2-input, 2-V to 5.5-V AND gate with open-drain outputs 5-SOT-23 -55 to 125")
      (fields (field (name "MANUFACTURER") "Texas Instruments"))
      (libsource (lib "28Pins_Project_V1I1") (part "SN74AHC1G09DBVR"))
    )
    (comp (ref "Y1")
      (value "ABM7-16.000MHZ-D2Y-T")
      (footprint "ABM_v1_I1_BIG")
      (description "Crystal 16MHz ±20ppm (Tol) ±30ppm (Stability) 18pF FUND 50Ohm 2-Pin Mini-CSMD T/R")
      (fields (field (name "MANUFACTURER") "Abracon") (field (name "TOLERANCE") "20ppm"))
      (libsource (lib "28Pins_Project_V1I1") (part "ABM7-16.000MHZ-D2Y-T"))
    )
    (comp (ref "Y2")
      (value "ABM7-16.000MHZ-D2Y-T")
      (footprint "ABM_v1_I1_BIG")
      (description "Crystal 16MHz ±20ppm (Tol) ±30ppm (Stability) 18pF FUND 50Ohm 2-Pin Mini-CSMD T/R")
      (fields (field (name "MANUFACTURER") "Abracon") (field (name "TOLERANCE") "20ppm"))
      (libsource (lib "28Pins_Project_V1I1") (part "ABM7-16.000MHZ-D2Y-T"))
    )
    (comp (ref "Z1")
      (value "CG0603MLC-05E")
      (footprint "R0603")
      (description "ESD Suppressor Multilayer Varistor 5V Automotive 2-Pin Case 0603(1608Metric) T/R")
      (fields (field (name "MANUFACTURER") "Bourns") (field (name "VOLTAGE") "5V"))
      (libsource (lib "28Pins_Project_V1I1") (part "CG0603MLC-05E"))
    )
    (comp (ref "Z2")
      (value "CG0603MLC-05E")
      (footprint "R0603")
      (description "ESD Suppressor Multilayer Varistor 5V Automotive 2-Pin Case 0603(1608Metric) T/R")
      (fields (field (name "MANUFACTURER") "Bourns") (field (name "VOLTAGE") "5V"))
      (libsource (lib "28Pins_Project_V1I1") (part "CG0603MLC-05E"))
    )
  )
  (nets
    (net (code "1") (name "+3V3") (class "Default")
      (node (ref "C14") (pin "2") (pinfunction "2_2") (pintype "passive"))
      (node (ref "C17") (pin "2") (pinfunction "2_2") (pintype "passive"))
      (node (ref "J1") (pin "4") (pinfunction "4_4") (pintype "passive"))
      (node (ref "JP4") (pin "1") (pinfunction "1_1") (pintype "passive"))
      (node (ref "R15") (pin "2") (pinfunction "2_2") (pintype "passive"))
      (node (ref "U2") (pin "4") (pinfunction "OUT_4") (pintype "passive"))
      (node (ref "U2") (pin "5") (pinfunction "SENSE_5") (pintype "passive"))
    )
    (net (code "2") (name "+5V") (class "Default")
      (node (ref "C12") (pin "2") (pinfunction "2_2") (pintype "passive"))
      (node (ref "C16") (pin "2") (pinfunction "2_2") (pintype "passive"))
      (node (ref "C4") (pin "2") (pinfunction "2_2") (pintype "passive"))
      (node (ref "C6") (pin "1") (pinfunction "1_1") (pintype "passive"))
      (node (ref "J1") (pin "5") (pinfunction "5_5") (pintype "passive"))
      (node (ref "J8") (pin "1") (pinfunction "1_1") (pintype "passive"))
      (node (ref "JP4") (pin "3") (pinfunction "3_3") (pintype "passive"))
      (node (ref "L1") (pin "2") (pinfunction "2_2") (pintype "passive"))
      (node (ref "R14") (pin "1") (pinfunction "1_1") (pintype "passive"))
      (node (ref "U1") (pin "31") (pinfunction "UVCC_31") (pintype "passive"))
      (node (ref "U2") (pin "1") (pinfunction "~{SHDN}_1") (pintype "passive"))
      (node (ref "U2") (pin "2") (pinfunction "IN_2") (pintype "passive"))
    )
    (net (code "3") (name "+5V{slash}3V3") (class "Default")
      (node (ref "C13") (pin "2") (pinfunction "2_2") (pintype "passive"))
      (node (ref "C15") (pin "2") (pinfunction "2_2") (pintype "passive"))
      (node (ref "C18") (pin "2") (pinfunction "2_2") (pintype "passive"))
      (node (ref "C25") (pin "2") (pinfunction "2_2") (pintype "passive"))
      (node (ref "C28") (pin "2") (pinfunction "2_2") (pintype "passive"))
      (node (ref "C30") (pin "2") (pinfunction "2_2") (pintype "passive"))
      (node (ref "C31") (pin "2") (pinfunction "2_2") (pintype "passive"))
      (node (ref "C8") (pin "2") (pinfunction "2_2") (pintype "passive"))
      (node (ref "D5") (pin "1") (pinfunction "Cathode_1") (pintype "passive"))
      (node (ref "D6") (pin "1") (pinfunction "Cathode_1") (pintype "passive"))
      (node (ref "FB1") (pin "1") (pinfunction "1_1") (pintype "passive"))
      (node (ref "FB2") (pin "1") (pinfunction "1_1") (pintype "passive"))
      (node (ref "FB3") (pin "1") (pinfunction "1_1") (pintype "passive"))
      (node (ref "J1") (pin "2") (pinfunction "2_2") (pintype "passive"))
      (node (ref "J5") (pin "2") (pinfunction "2_2") (pintype "passive"))
      (node (ref "J6") (pin "2") (pinfunction "2_2") (pintype "passive"))
      (node (ref "JP4") (pin "2") (pinfunction "2_2") (pintype "passive"))
      (node (ref "R1") (pin "2") (pinfunction "2_2") (pintype "passive"))
      (node (ref "R14") (pin "2") (pinfunction "2_2") (pintype "passive"))
      (node (ref "R15") (pin "1") (pinfunction "1_1") (pintype "passive"))
      (node (ref "R17") (pin "2") (pinfunction "2_2") (pintype "passive"))
      (node (ref "R18") (pin "2") (pinfunction "2_2") (pintype "passive"))
      (node (ref "R19") (pin "2") (pinfunction "2_2") (pintype "passive"))
      (node (ref "R2") (pin "2") (pinfunction "2_2") (pintype "passive"))
      (node (ref "R21") (pin "2") (pinfunction "2_2") (pintype "passive"))
      (node (ref "R23") (pin "2") (pinfunction "2_2") (pintype "passive"))
      (node (ref "R24") (pin "2") (pinfunction "2_2") (pintype "passive"))
      (node (ref "R25") (pin "2") (pinfunction "2_2") (pintype "passive"))
      (node (ref "R3") (pin "2") (pinfunction "2_2") (pintype "passive"))
      (node (ref "R5") (pin "2") (pinfunction "2_2") (pintype "passive"))
      (node (ref "U4") (pin "5") (pinfunction "5_5") (pintype "passive"))
      (node (ref "U5") (pin "5") (pinfunction "5_5") (pintype "passive"))
      (node (ref "U6") (pin "5") (pinfunction "5_5") (pintype "passive"))
      (node (ref "U7") (pin "5") (pinfunction "5_5") (pintype "passive"))
    )
    (net (code "4") (name "+AREF") (class "Default")
      (node (ref "C19") (pin "2") (pinfunction "2_2") (pintype "passive"))
      (node (ref "C24") (pin "2") (pinfunction "2_2") (pintype "passive"))
      (node (ref "J4") (pin "8") (pinfunction "8_8") (pintype "passive"))
      (node (ref "U3") (pin "21") (pinfunction "AREF_21") (pintype "passive"))
    )
    (net (code "5") (name "/+3V3_16U2_UCAP") (class "Default")
      (node (ref "C7") (pin "2") (pinfunction "2_2") (pintype "passive"))
      (node (ref "R4") (pin "1") (pinfunction "1_1") (pintype "passive"))
      (node (ref "U1") (pin "27") (pinfunction "UCAP_27") (pintype "passive"))
    )
    (net (code "6") (name "/+5V_USB") (class "Default")
      (node (ref "C5") (pin "1") (pinfunction "1_1") (pintype "passive"))
      (node (ref "J7") (pin "1") (pinfunction "1_1") (pintype "passive"))
      (node (ref "L1") (pin "1") (pinfunction "1_1") (pintype "passive"))
    )
    (net (code "7") (name "/+5{slash}3V3_16U2") (class "Default")
      (node (ref "C1") (pin "2") (pinfunction "2_2") (pintype "passive"))
      (node (ref "C2") (pin "2") (pinfunction "2_2") (pintype "passive"))
      (node (ref "C3") (pin "2") (pinfunction "2_2") (pintype "passive"))
      (node (ref "FB1") (pin "2") (pinfunction "2_2") (pintype "passive"))
      (node (ref "R4") (pin "2") (pinfunction "2_2") (pintype "passive"))
      (node (ref "U1") (pin "32") (pinfunction "AVCC_32") (pintype "passive"))
      (node (ref "U1") (pin "4") (pinfunction "VCC_4") (pintype "passive"))
    )
    (net (code "8") (name "/+5{slash}3V3_328P_AVCC") (class "Default")
      (node (ref "C22") (pin "2") (pinfunction "2_2") (pintype "passive"))
      (node (ref "C23") (pin "2") (pinfunction "2_2") (pintype "passive"))
      (node (ref "FB3") (pin "2") (pinfunction "2_2") (pintype "passive"))
      (node (ref "U3") (pin "20") (pinfunction "AVCC_20") (pintype "passive"))
    )
    (net (code "9") (name "/+5{slash}3V3_328P_VCC") (class "Default")
      (node (ref "C20") (pin "2") (pinfunction "2_2") (pintype "passive"))
      (node (ref "C21") (pin "2") (pinfunction "2_2") (pintype "passive"))
      (node (ref "FB2") (pin "2") (pinfunction "2_2") (pintype "passive"))
      (node (ref "U3") (pin "7") (pinfunction "VCC_7") (pintype "passive"))
    )
    (net (code "10") (name "/16U2PROG_328P_RESETn") (class "Default")
      (node (ref "JP1") (pin "2") (pinfunction "2_2") (pintype "passive"))
      (node (ref "R3") (pin "1") (pinfunction "1_1") (pintype "passive"))
      (node (ref "U1") (pin "13") (pinfunction "~{CTS}_/~{_HWB}_/_AIN6_/_T0_/_INT7_/_PD7_13") (pintype "passive"))
    )
    (net (code "11") (name "/16U2_16MHZ_XTAL1") (class "Default")
      (node (ref "C10") (pin "2") (pinfunction "2_2") (pintype "passive"))
      (node (ref "R10") (pin "1") (pinfunction "1_1") (pintype "passive"))
      (node (ref "U1") (pin "1") (pinfunction "XTAL1_1") (pintype "passive"))
      (node (ref "Y1") (pin "1") (pinfunction "1_1") (pintype "passive"))
    )
    (net (code "12") (name "/16U2_16MHZ_XTAL2") (class "Default")
      (node (ref "C9") (pin "2") (pinfunction "2_2") (pintype "passive"))
      (node (ref "R10") (pin "2") (pinfunction "2_2") (pintype "passive"))
      (node (ref "U1") (pin "2") (pinfunction "XTAL2_/_PC0_2") (pintype "passive"))
      (node (ref "Y1") (pin "2") (pinfunction "2_2") (pintype "passive"))
    )
    (net (code "13") (name "/16U2_BUF_RESETn") (class "Default")
      (node (ref "C29") (pin "2") (pinfunction "2_2") (pintype "passive"))
      (node (ref "R22") (pin "2") (pinfunction "2_2") (pintype "passive"))
      (node (ref "U5") (pin "1") (pinfunction "1_1") (pintype "passive"))
      (node (ref "U5") (pin "2") (pinfunction "2_2") (pintype "passive"))
    )
    (net (code "14") (name "/16U2_HDR_RESETn") (class "Default")
      (node (ref "J6") (pin "5") (pinfunction "5_5") (pintype "passive"))
      (node (ref "JP3") (pin "3") (pinfunction "3_3") (pintype "passive"))
    )
    (net (code "15") (name "/16U2_MISO") (class "Default")
      (node (ref "J6") (pin "1") (pinfunction "1_1") (pintype "passive"))
      (node (ref "U1") (pin "17") (pinfunction "PDO_/_MISO_/_PCINT3_/_PB3_17") (pintype "passive"))
    )
    (net (code "16") (name "/16U2_MOSI") (class "Default")
      (node (ref "J6") (pin "4") (pinfunction "4_4") (pintype "passive"))
      (node (ref "U1") (pin "16") (pinfunction "PDI_/_MOSI_/_PCINT2_/_PB2_16") (pintype "passive"))
    )
    (net (code "17") (name "/16U2_PB4") (class "Default")
      (node (ref "JP2") (pin "1") (pinfunction "1_1") (pintype "passive"))
      (node (ref "JP3") (pin "2") (pinfunction "2_2") (pintype "passive"))
      (node (ref "U1") (pin "18") (pinfunction "T1_/_PCINT4_/_PB4_18") (pintype "passive"))
    )
    (net (code "18") (name "/16U2_PB5") (class "Default")
      (node (ref "JP2") (pin "3") (pinfunction "3_3") (pintype "passive"))
      (node (ref "U1") (pin "19") (pinfunction "PCINT5_/_PB5_19") (pintype "passive"))
    )
    (net (code "19") (name "/16U2_PB6") (class "Default")
      (node (ref "JP2") (pin "2") (pinfunction "2_2") (pintype "passive"))
      (node (ref "U1") (pin "20") (pinfunction "PCINT6_/_PB6_20") (pintype "passive"))
    )
    (net (code "20") (name "/16U2_PB7") (class "Default")
      (node (ref "JP2") (pin "4") (pinfunction "4_4") (pintype "passive"))
      (node (ref "U1") (pin "21") (pinfunction "PCINT7_/_OC.0A_/_OC.1C_/_PB7_21") (pintype "passive"))
    )
    (net (code "21") (name "/16U2_RESETn") (class "Default")
      (node (ref "JP3") (pin "4") (pinfunction "4_4") (pintype "passive"))
      (node (ref "R5") (pin "1") (pinfunction "1_1") (pintype "passive"))
      (node (ref "U1") (pin "24") (pinfunction "PC1_/~{_Reset}_/_DW_24") (pintype "passive"))
      (node (ref "U5") (pin "4") (pinfunction "4_4") (pintype "passive"))
    )
    (net (code "22") (name "/16U2_RXD") (class "Default")
      (node (ref "R12") (pin "1") (pinfunction "1_1") (pintype "passive"))
      (node (ref "U1") (pin "8") (pinfunction "RXD1_/_AIN1_/_INT2_/_PD2_8") (pintype "passive"))
    )
    (net (code "23") (name "/16U2_RX_LED") (class "Default")
      (node (ref "D1") (pin "1") (pinfunction "Cathode_1") (pintype "passive"))
      (node (ref "U1") (pin "10") (pinfunction "INT5_/_AIN3_/_PD4_10") (pintype "passive"))
    )
    (net (code "24") (name "/16U2_SCLK") (class "Default")
      (node (ref "J6") (pin "3") (pinfunction "3_3") (pintype "passive"))
      (node (ref "R6") (pin "2") (pinfunction "2_2") (pintype "passive"))
    )
    (net (code "25") (name "/16U2_SCLK_R") (class "Default")
      (node (ref "R6") (pin "1") (pinfunction "1_1") (pintype "passive"))
      (node (ref "U1") (pin "15") (pinfunction "SCLK_/_PCINT1_/_PB1_15") (pintype "passive"))
    )
    (net (code "26") (name "/16U2_TXD") (class "Default")
      (node (ref "R11") (pin "1") (pinfunction "1_1") (pintype "passive"))
      (node (ref "U1") (pin "9") (pinfunction "TXD1_/_INT3_/_PD3_9") (pintype "passive"))
    )
    (net (code "27") (name "/16U2_TX_LED") (class "Default")
      (node (ref "D2") (pin "1") (pinfunction "Cathode_1") (pintype "passive"))
      (node (ref "U1") (pin "11") (pinfunction "XCK_AIN4_/_PCINT12_/_PD5_11") (pintype "passive"))
    )
    (net (code "28") (name "/328P_16MHZ_XTAL1") (class "Default")
      (node (ref "C27") (pin "2") (pinfunction "2_2") (pintype "passive"))
      (node (ref "R20") (pin "1") (pinfunction "1_1") (pintype "passive"))
      (node (ref "U3") (pin "9") (pinfunction "PB6_/_PCINT6_/_XTAL1_/_TOSC1_9") (pintype "passive"))
      (node (ref "Y2") (pin "1") (pinfunction "1_1") (pintype "passive"))
    )
    (net (code "29") (name "/328P_16MHZ_XTAL2") (class "Default")
      (node (ref "C26") (pin "2") (pinfunction "2_2") (pintype "passive"))
      (node (ref "R20") (pin "2") (pinfunction "2_2") (pintype "passive"))
      (node (ref "U3") (pin "10") (pinfunction "PB7_/_PCINT7_/_XTAL2_/_TOSC2_10") (pintype "passive"))
      (node (ref "Y2") (pin "2") (pinfunction "2_2") (pintype "passive"))
    )
    (net (code "30") (name "/328P_AUTORESETn") (class "Default")
      (node (ref "C11") (pin "1") (pinfunction "1_1") (pintype "passive"))
      (node (ref "R25") (pin "1") (pinfunction "1_1") (pintype "passive"))
      (node (ref "U6") (pin "1") (pinfunction "1_1") (pintype "passive"))
    )
    (net (code "31") (name "/328P_BUF_RESETn") (class "Default")
      (node (ref "C32") (pin "2") (pinfunction "2_2") (pintype "passive"))
      (node (ref "R28") (pin "2") (pinfunction "2_2") (pintype "passive"))
      (node (ref "U6") (pin "2") (pinfunction "2_2") (pintype "passive"))
    )
    (net (code "32") (name "/328P_RESETn") (class "Default")
      (node (ref "J1") (pin "3") (pinfunction "3_3") (pintype "passive"))
      (node (ref "J5") (pin "5") (pinfunction "5_5") (pintype "passive"))
      (node (ref "JP3") (pin "1") (pinfunction "1_1") (pintype "passive"))
      (node (ref "R19") (pin "1") (pinfunction "1_1") (pintype "passive"))
      (node (ref "U3") (pin "1") (pinfunction "PC6_/_PCINT14_/~{_RESET}_1") (pintype "passive"))
      (node (ref "U6") (pin "4") (pinfunction "4_4") (pintype "passive"))
    )
    (net (code "33") (name "/AD0") (class "Default")
      (node (ref "J2") (pin "1") (pinfunction "1_1") (pintype "passive"))
      (node (ref "U3") (pin "23") (pinfunction "ADC0_/_PCINT8_/_PC0_23") (pintype "passive"))
    )
    (net (code "34") (name "/AD1") (class "Default")
      (node (ref "J2") (pin "2") (pinfunction "2_2") (pintype "passive"))
      (node (ref "U3") (pin "24") (pinfunction "ADC1_/_PCINT9_/_PC1_24") (pintype "passive"))
    )
    (net (code "35") (name "/AD2") (class "Default")
      (node (ref "J2") (pin "3") (pinfunction "3_3") (pintype "passive"))
      (node (ref "U3") (pin "25") (pinfunction "ADC2_/_PCINT10_/_PC2_25") (pintype "passive"))
    )
    (net (code "36") (name "/AD3") (class "Default")
      (node (ref "J2") (pin "4") (pinfunction "4_4") (pintype "passive"))
      (node (ref "U3") (pin "26") (pinfunction "ADC3_/_PCINT11_/_PC3_26") (pintype "passive"))
    )
    (net (code "37") (name "/AD4{slash}SDA") (class "Default")
      (node (ref "J2") (pin "5") (pinfunction "5_5") (pintype "passive"))
      (node (ref "J4") (pin "9") (pinfunction "9_9") (pintype "passive"))
      (node (ref "U3") (pin "27") (pinfunction "ADC4_/_SDA_/_PCINT12_/_PC4_27") (pintype "passive"))
    )
    (net (code "38") (name "/AD5{slash}SCL") (class "Default")
      (node (ref "J2") (pin "6") (pinfunction "6_6") (pintype "passive"))
      (node (ref "J4") (pin "10") (pinfunction "10_10") (pintype "passive"))
      (node (ref "U3") (pin "28") (pinfunction "ADC5_/_SCL_/_PCINT13_/_PC5_28") (pintype "passive"))
    )
    (net (code "39") (name "/BUTTON_RESETn") (class "Default")
      (node (ref "D6") (pin "2") (pinfunction "Anode_2") (pintype "passive"))
      (node (ref "R23") (pin "1") (pinfunction "1_1") (pintype "passive"))
      (node (ref "R28") (pin "1") (pinfunction "1_1") (pintype "passive"))
      (node (ref "SW1") (pin "1") (pinfunction "1_1") (pintype "passive"))
      (node (ref "SW1") (pin "2") (pinfunction "2_2") (pintype "passive"))
    )
    (net (code "40") (name "/CON_USB_N") (class "Default")
      (node (ref "J7") (pin "2") (pinfunction "2_2") (pintype "passive"))
      (node (ref "R7") (pin "1") (pinfunction "1_1") (pintype "passive"))
      (node (ref "Z1") (pin "2") (pinfunction "2_2") (pintype "passive"))
    )
    (net (code "41") (name "/CON_USB_P") (class "Default")
      (node (ref "J7") (pin "3") (pinfunction "3_3") (pintype "passive"))
      (node (ref "R8") (pin "1") (pinfunction "1_1") (pintype "passive"))
      (node (ref "Z2") (pin "2") (pinfunction "2_2") (pintype "passive"))
    )
    (net (code "42") (name "/IO0") (class "Default")
      (node (ref "J3") (pin "1") (pinfunction "1_1") (pintype "passive"))
      (node (ref "R11") (pin "2") (pinfunction "2_2") (pintype "passive"))
      (node (ref "U3") (pin "2") (pinfunction "PCINT16_/_RXD_/_PD0_2") (pintype "passive"))
    )
    (net (code "43") (name "/IO1") (class "Default")
      (node (ref "J3") (pin "2") (pinfunction "2_2") (pintype "passive"))
      (node (ref "R12") (pin "2") (pinfunction "2_2") (pintype "passive"))
      (node (ref "U3") (pin "3") (pinfunction "PCINT17_/_TXD_/_PD1_3") (pintype "passive"))
    )
    (net (code "44") (name "/IO2") (class "Default")
      (node (ref "J3") (pin "3") (pinfunction "3_3") (pintype "passive"))
      (node (ref "U3") (pin "4") (pinfunction "PCINT18_/_INT0_/_PD2_4") (pintype "passive"))
    )
    (net (code "45") (name "/IO3") (class "Default")
      (node (ref "J3") (pin "4") (pinfunction "4_4") (pintype "passive"))
      (node (ref "U3") (pin "5") (pinfunction "PCINT19_/_OC2B_/_INT1_/_PD3_5") (pintype "passive"))
    )
    (net (code "46") (name "/IO4") (class "Default")
      (node (ref "J3") (pin "5") (pinfunction "5_5") (pintype "passive"))
      (node (ref "U3") (pin "6") (pinfunction "PCINT20_/_XCK_/_T0_/_PD4_6") (pintype "passive"))
    )
    (net (code "47") (name "/IO5") (class "Default")
      (node (ref "J3") (pin "6") (pinfunction "6_6") (pintype "passive"))
      (node (ref "U3") (pin "11") (pinfunction "PCINT21_/_OC0B_/_T1_/_PD5_11") (pintype "passive"))
    )
    (net (code "48") (name "/IO6") (class "Default")
      (node (ref "J3") (pin "7") (pinfunction "7_7") (pintype "passive"))
      (node (ref "U3") (pin "12") (pinfunction "PCINT22_/_OC0A_/_AIN0_/_PD6_12") (pintype "passive"))
    )
    (net (code "49") (name "/IO7") (class "Default")
      (node (ref "J3") (pin "8") (pinfunction "8_8") (pintype "passive"))
      (node (ref "U3") (pin "13") (pinfunction "PCINT23_/_AIN1_/_PD7_13") (pintype "passive"))
    )
    (net (code "50") (name "/IO8") (class "Default")
      (node (ref "J4") (pin "1") (pinfunction "1_1") (pintype "passive"))
      (node (ref "R26") (pin "2") (pinfunction "2_2") (pintype "passive"))
      (node (ref "U3") (pin "14") (pinfunction "PCINT0_/_CLKO_/_ICP1_/_PB0_14") (pintype "passive"))
    )
    (net (code "51") (name "/IO9") (class "Default")
      (node (ref "J4") (pin "2") (pinfunction "2_2") (pintype "passive"))
      (node (ref "U3") (pin "15") (pinfunction "OC1A_/_PCINT1_/_PB1_15") (pintype "passive"))
    )
    (net (code "52") (name "/MISO") (class "Default")
      (node (ref "J4") (pin "5") (pinfunction "5_5") (pintype "passive"))
      (node (ref "J5") (pin "1") (pinfunction "1_1") (pintype "passive"))
      (node (ref "U3") (pin "18") (pinfunction "MISO_/_PCINT4_/_PB4_18") (pintype "passive"))
    )
    (net (code "53") (name "/MOSI") (class "Default")
      (node (ref "J4") (pin "4") (pinfunction "4_4") (pintype "passive"))
      (node (ref "J5") (pin "4") (pinfunction "4_4") (pintype "passive"))
      (node (ref "U3") (pin "17") (pinfunction "MOSI_/_OC2A_/_PCINT3_/_PB3_17") (pintype "passive"))
    )
    (net (code "54") (name "/SCK") (class "Default")
      (node (ref "J4") (pin "6") (pinfunction "6_6") (pintype "passive"))
      (node (ref "J5") (pin "3") (pinfunction "3_3") (pintype "passive"))
      (node (ref "R16") (pin "2") (pinfunction "2_2") (pintype "passive"))
      (node (ref "U4") (pin "1") (pinfunction "1_1") (pintype "passive"))
      (node (ref "U4") (pin "2") (pinfunction "2_2") (pintype "passive"))
    )
    (net (code "55") (name "/SCK_R") (class "Default")
      (node (ref "R16") (pin "1") (pinfunction "1_1") (pintype "passive"))
      (node (ref "U3") (pin "19") (pinfunction "SCK_/_PCINT5_/_PB5_19") (pintype "passive"))
    )
    (net (code "56") (name "/SS") (class "Default")
      (node (ref "J4") (pin "3") (pinfunction "3_3") (pintype "passive"))
      (node (ref "U3") (pin "16") (pinfunction "~{SS}_/_OC1B_/_PCINT2_/_PB2_16") (pintype "passive"))
    )
    (net (code "57") (name "/USB_N") (class "Default")
      (node (ref "R7") (pin "2") (pinfunction "2_2") (pintype "passive"))
      (node (ref "U1") (pin "30") (pinfunction "D-_30") (pintype "passive"))
    )
    (net (code "58") (name "/USB_P") (class "Default")
      (node (ref "R8") (pin "2") (pinfunction "2_2") (pintype "passive"))
      (node (ref "U1") (pin "29") (pinfunction "D+_29") (pintype "passive"))
    )
    (net (code "59") (name "/USER_BUTTON") (class "Default")
      (node (ref "R24") (pin "1") (pinfunction "1_1") (pintype "passive"))
      (node (ref "R27") (pin "1") (pinfunction "1_1") (pintype "passive"))
      (node (ref "SW2") (pin "1") (pinfunction "1_1") (pintype "passive"))
      (node (ref "SW2") (pin "2") (pinfunction "2_2") (pintype "passive"))
    )
    (net (code "60") (name "/USER_BUTTON_BUF") (class "Default")
      (node (ref "C33") (pin "2") (pinfunction "2_2") (pintype "passive"))
      (node (ref "R27") (pin "2") (pinfunction "2_2") (pintype "passive"))
      (node (ref "U7") (pin "1") (pinfunction "1_1") (pintype "passive"))
      (node (ref "U7") (pin "2") (pinfunction "2_2") (pintype "passive"))
    )
    (net (code "61") (name "GND") (class "Default")
      (node (ref "C1") (pin "1") (pinfunction "1_1") (pintype "passive"))
      (node (ref "C10") (pin "1") (pinfunction "1_1") (pintype "passive"))
      (node (ref "C12") (pin "1") (pinfunction "1_1") (pintype "passive"))
      (node (ref "C13") (pin "1") (pinfunction "1_1") (pintype "passive"))
      (node (ref "C14") (pin "1") (pinfunction "1_1") (pintype "passive"))
      (node (ref "C15") (pin "1") (pinfunction "1_1") (pintype "passive"))
      (node (ref "C16") (pin "1") (pinfunction "1_1") (pintype "passive"))
      (node (ref "C17") (pin "1") (pinfunction "1_1") (pintype "passive"))
      (node (ref "C18") (pin "1") (pinfunction "1_1") (pintype "passive"))
      (node (ref "C19") (pin "1") (pinfunction "1_1") (pintype "passive"))
      (node (ref "C2") (pin "1") (pinfunction "1_1") (pintype "passive"))
      (node (ref "C20") (pin "1") (pinfunction "1_1") (pintype "passive"))
      (node (ref "C21") (pin "1") (pinfunction "1_1") (pintype "passive"))
      (node (ref "C22") (pin "1") (pinfunction "1_1") (pintype "passive"))
      (node (ref "C23") (pin "1") (pinfunction "1_1") (pintype "passive"))
      (node (ref "C24") (pin "1") (pinfunction "1_1") (pintype "passive"))
      (node (ref "C25") (pin "1") (pinfunction "1_1") (pintype "passive"))
      (node (ref "C26") (pin "1") (pinfunction "1_1") (pintype "passive"))
      (node (ref "C27") (pin "1") (pinfunction "1_1") (pintype "passive"))
      (node (ref "C28") (pin "1") (pinfunction "1_1") (pintype "passive"))
      (node (ref "C29") (pin "1") (pinfunction "1_1") (pintype "passive"))
      (node (ref "C3") (pin "1") (pinfunction "1_1") (pintype "passive"))
      (node (ref "C30") (pin "1") (pinfunction "1_1") (pintype "passive"))
      (node (ref "C31") (pin "1") (pinfunction "1_1") (pintype "passive"))
      (node (ref "C32") (pin "1") (pinfunction "1_1") (pintype "passive"))
      (node (ref "C33") (pin "1") (pinfunction "1_1") (pintype "passive"))
      (node (ref "C4") (pin "1") (pinfunction "1_1") (pintype "passive"))
      (node (ref "C5") (pin "2") (pinfunction "2_2") (pintype "passive"))
      (node (ref "C6") (pin "2") (pinfunction "2_2") (pintype "passive"))
      (node (ref "C7") (pin "1") (pinfunction "1_1") (pintype "passive"))
      (node (ref "C8") (pin "1") (pinfunction "1_1") (pintype "passive"))
      (node (ref "C9") (pin "1") (pinfunction "1_1") (pintype "passive"))
      (node (ref "D4") (pin "1") (pinfunction "Cathode_1") (pintype "passive"))
      (node (ref "J1") (pin "6") (pinfunction "6_6") (pintype "passive"))
      (node (ref "J1") (pin "7") (pinfunction "7_7") (pintype "passive"))
      (node (ref "J4") (pin "7") (pinfunction "7_7") (pintype "passive"))
      (node (ref "J5") (pin "6") (pinfunction "6_6") (pintype "passive"))
      (node (ref "J6") (pin "6") (pinfunction "6_6") (pintype "passive"))
      (node (ref "J7") (pin "10") (pinfunction "10_10") (pintype "passive"))
      (node (ref "J7") (pin "11") (pinfunction "11_11") (pintype "passive"))
      (node (ref "J7") (pin "5") (pinfunction "5_5") (pintype "passive"))
      (node (ref "J7") (pin "6") (pinfunction "6_6") (pintype "passive"))
      (node (ref "J7") (pin "7") (pinfunction "7_7") (pintype "passive"))
      (node (ref "J7") (pin "8") (pinfunction "8_8") (pintype "passive"))
      (node (ref "J7") (pin "9") (pinfunction "9_9") (pintype "passive"))
      (node (ref "J9") (pin "1") (pinfunction "1_1") (pintype "passive"))
      (node (ref "MH1") (pin "1") (pinfunction "1_1") (pintype "passive"))
      (node (ref "MH2") (pin "1") (pinfunction "1_1") (pintype "passive"))
      (node (ref "MH3") (pin "1") (pinfunction "1_1") (pintype "passive"))
      (node (ref "R13") (pin "1") (pinfunction "1_1") (pintype "passive"))
      (node (ref "R9") (pin "2") (pinfunction "2_2") (pintype "passive"))
      (node (ref "SW1") (pin "3") (pinfunction "3_3") (pintype "passive"))
      (node (ref "SW1") (pin "4") (pinfunction "4_4") (pintype "passive"))
      (node (ref "SW2") (pin "3") (pinfunction "3_3") (pintype "passive"))
      (node (ref "SW2") (pin "4") (pinfunction "4_4") (pintype "passive"))
      (node (ref "U1") (pin "28") (pinfunction "UGND_28") (pintype "passive"))
      (node (ref "U1") (pin "3") (pinfunction "GND_3") (pintype "passive"))
      (node (ref "U2") (pin "3") (pinfunction "GND_3") (pintype "passive"))
      (node (ref "U2") (pin "6") (pinfunction "EPAD_6") (pintype "passive"))
      (node (ref "U3") (pin "22") (pinfunction "GND_2_22") (pintype "passive"))
      (node (ref "U3") (pin "8") (pinfunction "GND_1_8") (pintype "passive"))
      (node (ref "U4") (pin "3") (pinfunction "3_3") (pintype "passive"))
      (node (ref "U5") (pin "3") (pinfunction "3_3") (pintype "passive"))
      (node (ref "U6") (pin "3") (pinfunction "3_3") (pintype "passive"))
      (node (ref "U7") (pin "3") (pinfunction "3_3") (pintype "passive"))
      (node (ref "Z1") (pin "1") (pinfunction "1_1") (pintype "passive"))
      (node (ref "Z2") (pin "1") (pinfunction "1_1") (pintype "passive"))
    )
    (net (code "62") (name "Net-(C11-Pad2)") (class "Default")
      (node (ref "C11") (pin "2") (pinfunction "2_2") (pintype "passive"))
      (node (ref "JP1") (pin "1") (pinfunction "1_1") (pintype "passive"))
    )
    (net (code "63") (name "Net-(D1-Anode)") (class "Default")
      (node (ref "D1") (pin "2") (pinfunction "Anode_2") (pintype "passive"))
      (node (ref "R1") (pin "1") (pinfunction "1_1") (pintype "passive"))
    )
    (net (code "64") (name "Net-(D2-Anode)") (class "Default")
      (node (ref "D2") (pin "2") (pinfunction "Anode_2") (pintype "passive"))
      (node (ref "R2") (pin "1") (pinfunction "1_1") (pintype "passive"))
    )
    (net (code "65") (name "Net-(D3-Anode)") (class "Default")
      (node (ref "D3") (pin "2") (pinfunction "Anode_2") (pintype "passive"))
      (node (ref "R17") (pin "1") (pinfunction "1_1") (pintype "passive"))
    )
    (net (code "66") (name "Net-(D3-Cathode)") (class "Default")
      (node (ref "D3") (pin "1") (pinfunction "Cathode_1") (pintype "passive"))
      (node (ref "U4") (pin "4") (pinfunction "4_4") (pintype "passive"))
    )
    (net (code "67") (name "Net-(D4-Anode)") (class "Default")
      (node (ref "D4") (pin "2") (pinfunction "Anode_2") (pintype "passive"))
      (node (ref "R18") (pin "1") (pinfunction "1_1") (pintype "passive"))
    )
    (net (code "68") (name "Net-(D5-Anode)") (class "Default")
      (node (ref "D5") (pin "2") (pinfunction "Anode_2") (pintype "passive"))
      (node (ref "R21") (pin "1") (pinfunction "1_1") (pintype "passive"))
      (node (ref "R22") (pin "1") (pinfunction "1_1") (pintype "passive"))
    )
    (net (code "69") (name "Net-(J7-Pad4)") (class "Default")
      (node (ref "J7") (pin "4") (pinfunction "4_4") (pintype "passive"))
      (node (ref "R9") (pin "1") (pinfunction "1_1") (pintype "passive"))
    )
    (net (code "70") (name "Net-(JP1-Pad3)") (class "Default")
      (node (ref "JP1") (pin "3") (pinfunction "3_3") (pintype "passive"))
      (node (ref "R13") (pin "2") (pinfunction "2_2") (pintype "passive"))
    )
    (net (code "71") (name "Net-(R26-Pad1)") (class "Default")
      (node (ref "R26") (pin "1") (pinfunction "1_1") (pintype "passive"))
      (node (ref "U7") (pin "4") (pinfunction "4_4") (pintype "passive"))
    )
    (net (code "72") (name "unconnected-(J1-Pad1)") (class "Default")
      (node (ref "J1") (pin "1") (pinfunction "1_1") (pintype "passive+no_connect"))
    )
    (net (code "73") (name "unconnected-(J1-Pad8)") (class "Default")
      (node (ref "J1") (pin "8") (pinfunction "8_8") (pintype "passive+no_connect"))
    )
    (net (code "74") (name "unconnected-(MH4-Pad1)") (class "Default")
      (node (ref "MH4") (pin "1") (pinfunction "1_1") (pintype "passive+no_connect"))
    )
    (net (code "75") (name "unconnected-(U1-AIN0_{slash}_INT1_{slash}_PD1-Pad7)") (class "Default")
      (node (ref "U1") (pin "7") (pinfunction "AIN0_/_INT1_/_PD1_7") (pintype "passive+no_connect"))
    )
    (net (code "76") (name "unconnected-(U1-INT4_{slash}_ICP1_{slash}_CLKO_{slash}_PC7-Pad22)") (class "Default")
      (node (ref "U1") (pin "22") (pinfunction "INT4_/_ICP1_/_CLKO_/_PC7_22") (pintype "passive+no_connect"))
    )
    (net (code "77") (name "unconnected-(U1-OC.0B_{slash}_INT0_{slash}_PD0-Pad6)") (class "Default")
      (node (ref "U1") (pin "6") (pinfunction "OC.0B_/_INT0_/_PD0_6") (pintype "passive+no_connect"))
    )
    (net (code "78") (name "unconnected-(U1-OC.1A_{slash}_PCINT8_{slash}_PC6-Pad23)") (class "Default")
      (node (ref "U1") (pin "23") (pinfunction "OC.1A_/_PCINT8_/_PC6_23") (pintype "passive+no_connect"))
    )
    (net (code "79") (name "unconnected-(U1-PCINT9{slash}_OC.1B_{slash}_PC5-Pad25)") (class "Default")
      (node (ref "U1") (pin "25") (pinfunction "PCINT9/_OC.1B_/_PC5_25") (pintype "passive+no_connect"))
    )
    (net (code "80") (name "unconnected-(U1-PCINT10_{slash}_PC4-Pad26)") (class "Default")
      (node (ref "U1") (pin "26") (pinfunction "PCINT10_/_PC4_26") (pintype "passive+no_connect"))
    )
    (net (code "81") (name "unconnected-(U1-PCINT11_{slash}AIN2_{slash}_PC2-Pad5)") (class "Default")
      (node (ref "U1") (pin "5") (pinfunction "PCINT11_/AIN2_/_PC2_5") (pintype "passive+no_connect"))
    )
    (net (code "82") (name "unconnected-(U1-~{RTS}_{slash}_AIN5_{slash}_INT6_{slash}_PD6-Pad12)") (class "Default")
      (node (ref "U1") (pin "12") (pinfunction "~{RTS}_/_AIN5_/_INT6_/_PD6_12") (pintype "passive+no_connect"))
    )
    (net (code "83") (name "unconnected-(U1-~{SS}_{slash}_PCINT0_{slash}_PB0-Pad14)") (class "Default")
      (node (ref "U1") (pin "14") (pinfunction "~{SS}_/_PCINT0_/_PB0_14") (pintype "passive+no_connect"))
    )
  )
)
